# ATtiny_prog_board.net
KiCad netlist of a schematic drawn in EAGLE
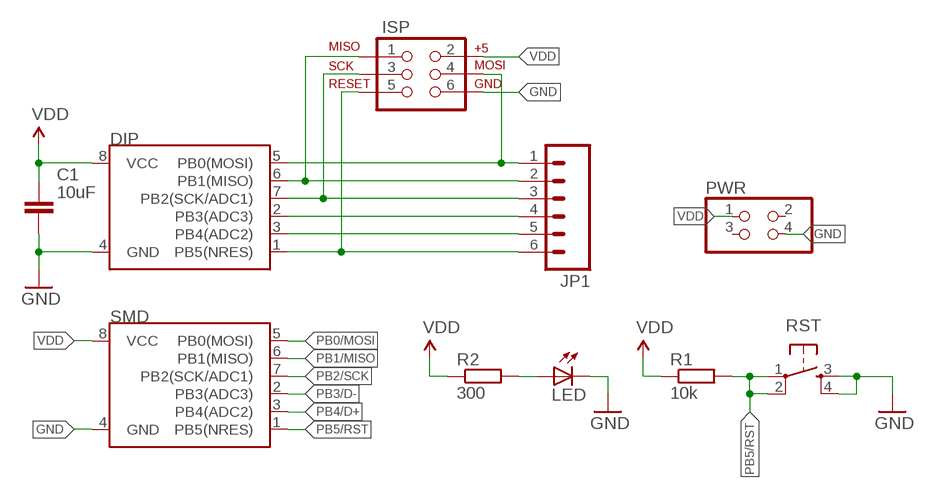
[diagram p0: schematic, sheet 1]

(export (version "E")
  (design (tool "Eeschema 10.0.6"))
  (components
    (comp (ref "C1")
      (value "10uF")
      (footprint "eagle-import:C805")
      (libsource (lib "eagle-import") (part "CAPACITOR_NPOL-0805"))
    )
    (comp (ref "DIP")
      (value "ATTINY45TINY85-20-DIP")
      (footprint "eagle-import:DIP08")
      (libsource (lib "eagle-import") (part "ATTINY45TINY85-20-DIP"))
    )
    (comp (ref "ISP")
      (value "AVR_SPI_PRG_6PTH")
      (footprint "eagle-import:2X3")
      (libsource (lib "eagle-import") (part "AVR_SPI_PRG_6PTH"))
    )
    (comp (ref "JP1")
      (value "M06SILK_FEMALE_PTH")
      (footprint "eagle-import:1X06")
      (libsource (lib "eagle-import") (part "M06SILK_FEMALE_PTH"))
    )
    (comp (ref "LED")
      (value "LED-0603")
      (footprint "eagle-import:LED-603")
      (libsource (lib "eagle-import") (part "LED-0603"))
    )
    (comp (ref "PWR")
      (value "PINHD-2X2")
      (footprint "eagle-import:2X02")
      (libsource (lib "eagle-import") (part "PINHD-2X2"))
    )
    (comp (ref "R1")
      (value "10k")
      (footprint "eagle-import:R603")
      (libsource (lib "eagle-import") (part "RESISTOR-0603"))
    )
    (comp (ref "R2")
      (value "300")
      (footprint "eagle-import:R603")
      (libsource (lib "eagle-import") (part "RESISTOR-0603"))
    )
    (comp (ref "RST")
      (value "TAC_SWITCHPTH")
      (footprint "eagle-import:TACTILE-PTH")
      (libsource (lib "eagle-import") (part "TAC_SWITCHPTH"))
    )
    (comp (ref "SMD")
      (value "ATTINY45TINY85-20-SMT")
      (footprint "eagle-import:SO08-EIAJ")
      (libsource (lib "eagle-import") (part "ATTINY45TINY85-20-SMT"))
    )
  )
  (nets
    (net (code "1") (name "GND") (class "Default")
      (node (ref "C1") (pin "2") (pinfunction "2_2") (pintype "passive"))
      (node (ref "DIP") (pin "4") (pinfunction "GND_4") (pintype "bidirectional"))
      (node (ref "ISP") (pin "6") (pinfunction "6_6") (pintype "passive"))
      (node (ref "LED") (pin "C") (pinfunction "C_C") (pintype "passive"))
      (node (ref "PWR") (pin "4") (pinfunction "4_4") (pintype "passive"))
      (node (ref "RST") (pin "3") (pinfunction "3_3") (pintype "passive"))
      (node (ref "RST") (pin "4") (pinfunction "4_4") (pintype "passive"))
      (node (ref "SMD") (pin "4") (pinfunction "GND_4") (pintype "bidirectional"))
    )
    (net (code "2") (name "Net-(LED-PadA)") (class "Default")
      (node (ref "LED") (pin "A") (pinfunction "A_A") (pintype "passive"))
      (node (ref "R2") (pin "2") (pinfunction "2_2") (pintype "passive"))
    )
    (net (code "3") (name "PB0{slash}MOSI") (class "Default")
      (node (ref "DIP") (pin "5") (pinfunction "PB0(MOSI)_5") (pintype "bidirectional"))
      (node (ref "ISP") (pin "4") (pinfunction "4_4") (pintype "passive"))
      (node (ref "JP1") (pin "1") (pinfunction "1_1") (pintype "passive"))
      (node (ref "SMD") (pin "5") (pinfunction "PB0(MOSI)_5") (pintype "bidirectional"))
    )
    (net (code "4") (name "PB1{slash}MISO") (class "Default")
      (node (ref "DIP") (pin "6") (pinfunction "PB1(MISO)_6") (pintype "bidirectional"))
      (node (ref "ISP") (pin "1") (pinfunction "1_1") (pintype "passive"))
      (node (ref "JP1") (pin "2") (pinfunction "2_2") (pintype "passive"))
      (node (ref "SMD") (pin "6") (pinfunction "PB1(MISO)_6") (pintype "bidirectional"))
    )
    (net (code "5") (name "PB2{slash}SCK") (class "Default")
      (node (ref "DIP") (pin "7") (pinfunction "PB2(SCK/ADC1)_7") (pintype "bidirectional"))
      (node (ref "ISP") (pin "3") (pinfunction "3_3") (pintype "passive"))
      (node (ref "JP1") (pin "3") (pinfunction "3_3") (pintype "passive"))
      (node (ref "SMD") (pin "7") (pinfunction "PB2(SCK/ADC1)_7") (pintype "bidirectional"))
    )
    (net (code "6") (name "PB3{slash}D-") (class "Default")
      (node (ref "DIP") (pin "2") (pinfunction "PB3(ADC3)_2") (pintype "bidirectional"))
      (node (ref "JP1") (pin "4") (pinfunction "4_4") (pintype "passive"))
      (node (ref "SMD") (pin "2") (pinfunction "PB3(ADC3)_2") (pintype "bidirectional"))
    )
    (net (code "7") (name "PB4{slash}D+") (class "Default")
      (node (ref "DIP") (pin "3") (pinfunction "PB4(ADC2)_3") (pintype "bidirectional"))
      (node (ref "JP1") (pin "5") (pinfunction "5_5") (pintype "passive"))
      (node (ref "SMD") (pin "3") (pinfunction "PB4(ADC2)_3") (pintype "bidirectional"))
    )
    (net (code "8") (name "PB5{slash}RST") (class "Default")
      (node (ref "DIP") (pin "1") (pinfunction "PB5(NRES)_1") (pintype "bidirectional"))
      (node (ref "ISP") (pin "5") (pinfunction "5_5") (pintype "passive"))
      (node (ref "JP1") (pin "6") (pinfunction "6_6") (pintype "passive"))
      (node (ref "R1") (pin "2") (pinfunction "2_2") (pintype "passive"))
      (node (ref "RST") (pin "1") (pinfunction "1_1") (pintype "passive"))
      (node (ref "RST") (pin "2") (pinfunction "2_2") (pintype "passive"))
      (node (ref "SMD") (pin "1") (pinfunction "PB5(NRES)_1") (pintype "bidirectional"))
    )
    (net (code "9") (name "VDD") (class "Default")
      (node (ref "C1") (pin "1") (pinfunction "1_1") (pintype "passive"))
      (node (ref "DIP") (pin "8") (pinfunction "VCC_8") (pintype "bidirectional"))
      (node (ref "ISP") (pin "2") (pinfunction "2_2") (pintype "passive"))
      (node (ref "PWR") (pin "1") (pinfunction "1_1") (pintype "passive"))
      (node (ref "R1") (pin "1") (pinfunction "1_1") (pintype "passive"))
      (node (ref "R2") (pin "1") (pinfunction "1_1") (pintype "passive"))
      (node (ref "SMD") (pin "8") (pinfunction "VCC_8") (pintype "bidirectional"))
    )
    (net (code "10") (name "unconnected-(PWR-Pad2)") (class "Default")
      (node (ref "PWR") (pin "2") (pinfunction "2_2") (pintype "passive"))
    )
    (net (code "11") (name "unconnected-(PWR-Pad3)") (class "Default")
      (node (ref "PWR") (pin "3") (pinfunction "3_3") (pintype "passive"))
    )
  )
)
